# TRIG_DIST.net
KiCad netlist of a schematic drawn in Altium Designer
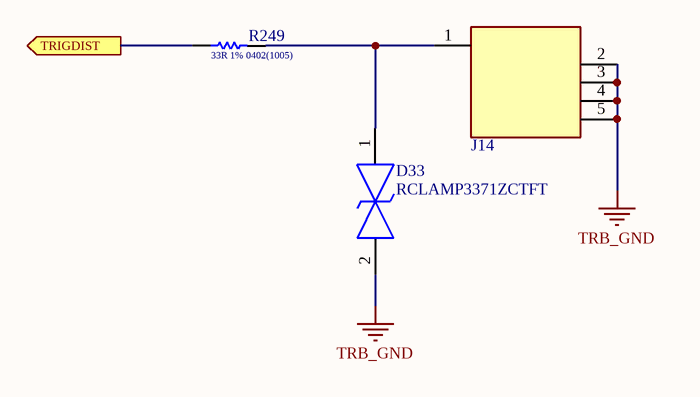
[diagram p0: TRIG_DIST.SchDoc]

(export (version "E")
  (design (tool "Eeschema 10.0.6"))
  (components
    (comp (ref "D33")
      (value "RCLAMP3371ZCTFT")
      (footprint "SamacSys:RCLAMP3371ZCTFT")
      (description "TVS Diode (Bi-directional)")
      (fields (field (name "MOUSER PART NUMBER") "947-RCLAMP3371ZCTFT"))
      (libsource (lib "*") (part "RCLAMP3371ZCTFT"))
    )
    (comp (ref "J14")
      (value "SMA JACK 50 OHM")
      (footprint "Amphenol_132289_0")
      (description "CONN SMA JACK 50 OHM EDGE MNT")
      (fields (field (name "MANUFACTURER") "Amphenol") (field (name "MOUSER PART NUMBER") "523-132289"))
      (libsource (lib "Conn_Amphenol_132289_eec") (part "Conn_Amphenol_132289_eec"))
    )
    (comp (ref "R249")
      (value "33R 1% 0402(1005)")
      (footprint "RESC0402(1005)_L")
      (description "33R 0.063W 1% 0402 (1005 Metric)  SMD")
      (fields (field (name "TOLERANCE") "1 %") (field (name "POWER") "0.063 W"))
      (libsource (lib "Altium Content Vault") (part "RES"))
    )
  )
  (nets
    (net (code "1") (name "/TRIGDIST") (class "Default")
      (node (ref "R249") (pin "1") (pinfunction "1_1") (pintype "passive"))
    )
    (net (code "2") (name "Net-(D33-Pad1)") (class "Default")
      (node (ref "D33") (pin "1") (pinfunction "1_1") (pintype "passive"))
      (node (ref "J14") (pin "1") (pinfunction "1_1") (pintype "passive"))
      (node (ref "R249") (pin "2") (pinfunction "2_2") (pintype "passive"))
    )
    (net (code "3") (name "TRB_GND") (class "Default")
      (node (ref "D33") (pin "2") (pinfunction "2_2") (pintype "passive"))
      (node (ref "J14") (pin "2") (pinfunction "MNT_1_2") (pintype "passive"))
      (node (ref "J14") (pin "3") (pinfunction "MNT_2_3") (pintype "passive"))
      (node (ref "J14") (pin "4") (pinfunction "MNT_3_4") (pintype "passive"))
      (node (ref "J14") (pin "5") (pinfunction "MNT_4_5") (pintype "passive"))
    )
  )
)
